# conbrio_pots_board_11-1-21.net
KiCad netlist of a schematic drawn in EAGLE
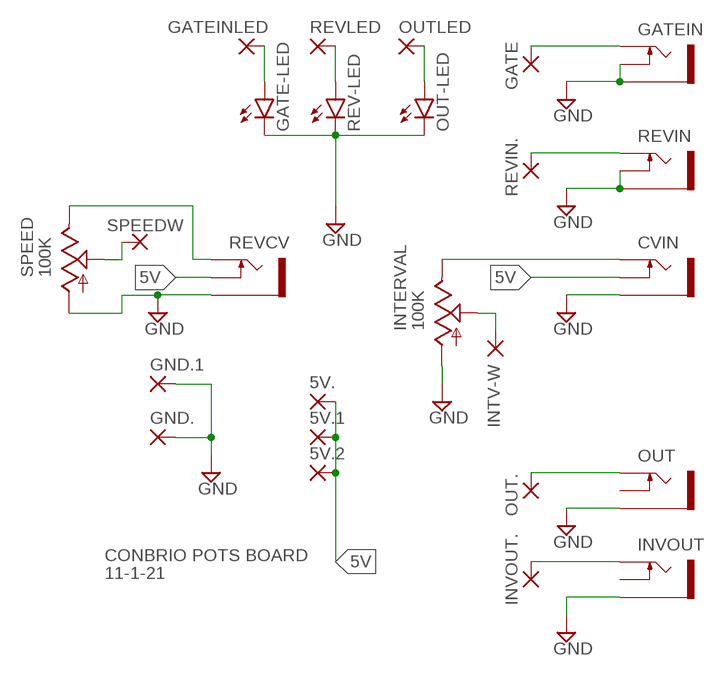
[diagram p0: schematic, sheet 1]

(export (version "E")
  (design (tool "Eeschema 10.0.6"))
  (components
    (comp (ref "5V.")
      (value "WIREPAD3,17/1,3")
      (footprint "eagle-import:3,17_1,3")
      (libsource (lib "eagle-import") (part "WIREPAD3,17/1,3"))
    )
    (comp (ref "5V.1")
      (value "WIREPAD3,17/1,3")
      (footprint "eagle-import:3,17_1,3")
      (libsource (lib "eagle-import") (part "WIREPAD3,17/1,3"))
    )
    (comp (ref "5V.2")
      (value "WIREPAD3,17/1,3")
      (footprint "eagle-import:3,17_1,3")
      (libsource (lib "eagle-import") (part "WIREPAD3,17/1,3"))
    )
    (comp (ref "CVIN")
      (value "THONKICONNNEW")
      (footprint "eagle-import:WQP-PJ301M-12_JACK")
      (libsource (lib "eagle-import") (part "THONKICONNNEW"))
    )
    (comp (ref "GATE")
      (value "WIREPAD3,17/1,3")
      (footprint "eagle-import:3,17_1,3")
      (libsource (lib "eagle-import") (part "WIREPAD3,17/1,3"))
    )
    (comp (ref "GATE-LED")
      (value "LED3MM")
      (footprint "eagle-import:LED3MM")
      (libsource (lib "eagle-import") (part "LED3MM"))
    )
    (comp (ref "GATEIN")
      (value "THONKICONNNEW")
      (footprint "eagle-import:WQP-PJ301M-12_JACK")
      (libsource (lib "eagle-import") (part "THONKICONNNEW"))
    )
    (comp (ref "GATEINLED")
      (value "WIREPAD3,17/1,3")
      (footprint "eagle-import:3,17_1,3")
      (libsource (lib "eagle-import") (part "WIREPAD3,17/1,3"))
    )
    (comp (ref "GND.")
      (value "WIREPAD3,17/1,3")
      (footprint "eagle-import:3,17_1,3")
      (libsource (lib "eagle-import") (part "WIREPAD3,17/1,3"))
    )
    (comp (ref "GND.1")
      (value "WIREPAD3,17/1,3")
      (footprint "eagle-import:3,17_1,3")
      (libsource (lib "eagle-import") (part "WIREPAD3,17/1,3"))
    )
    (comp (ref "INTERVAL")
      (value "100K")
      (footprint "eagle-import:9MM_SNAP-IN_POT")
      (libsource (lib "eagle-import") (part "9MM_SNAP-IN_POT_"))
    )
    (comp (ref "INTV-W")
      (value "WIREPAD3,17/1,3")
      (footprint "eagle-import:3,17_1,3")
      (libsource (lib "eagle-import") (part "WIREPAD3,17/1,3"))
    )
    (comp (ref "INVOUT")
      (value "THONKICONNNEW")
      (footprint "eagle-import:WQP-PJ301M-12_JACK")
      (libsource (lib "eagle-import") (part "THONKICONNNEW"))
    )
    (comp (ref "INVOUT.")
      (value "WIREPAD3,17/1,3")
      (footprint "eagle-import:3,17_1,3")
      (libsource (lib "eagle-import") (part "WIREPAD3,17/1,3"))
    )
    (comp (ref "OUT")
      (value "THONKICONNNEW")
      (footprint "eagle-import:WQP-PJ301M-12_JACK")
      (libsource (lib "eagle-import") (part "THONKICONNNEW"))
    )
    (comp (ref "OUT-LED")
      (value "LED3MM")
      (footprint "eagle-import:LED3MM")
      (libsource (lib "eagle-import") (part "LED3MM"))
    )
    (comp (ref "OUT.")
      (value "WIREPAD3,17/1,3")
      (footprint "eagle-import:3,17_1,3")
      (libsource (lib "eagle-import") (part "WIREPAD3,17/1,3"))
    )
    (comp (ref "OUTLED")
      (value "WIREPAD3,17/1,3")
      (footprint "eagle-import:3,17_1,3")
      (libsource (lib "eagle-import") (part "WIREPAD3,17/1,3"))
    )
    (comp (ref "REV-LED")
      (value "LED3MM")
      (footprint "eagle-import:LED3MM")
      (libsource (lib "eagle-import") (part "LED3MM"))
    )
    (comp (ref "REVCV")
      (value "THONKICONNNEW")
      (footprint "eagle-import:WQP-PJ301M-12_JACK")
      (libsource (lib "eagle-import") (part "THONKICONNNEW"))
    )
    (comp (ref "REVIN")
      (value "THONKICONNNEW")
      (footprint "eagle-import:WQP-PJ301M-12_JACK")
      (libsource (lib "eagle-import") (part "THONKICONNNEW"))
    )
    (comp (ref "REVIN.")
      (value "WIREPAD3,17/1,3")
      (footprint "eagle-import:3,17_1,3")
      (libsource (lib "eagle-import") (part "WIREPAD3,17/1,3"))
    )
    (comp (ref "REVLED")
      (value "WIREPAD3,17/1,3")
      (footprint "eagle-import:3,17_1,3")
      (libsource (lib "eagle-import") (part "WIREPAD3,17/1,3"))
    )
    (comp (ref "SPEED")
      (value "100K")
      (footprint "eagle-import:9MM_SNAP-IN_POT")
      (libsource (lib "eagle-import") (part "9MM_SNAP-IN_POT_"))
    )
    (comp (ref "SPEEDW")
      (value "WIREPAD3,17/1,3")
      (footprint "eagle-import:3,17_1,3")
      (libsource (lib "eagle-import") (part "WIREPAD3,17/1,3"))
    )
  )
  (nets
    (net (code "1") (name "5V") (class "Default")
      (node (ref "5V.") (pin "1") (pinfunction "P_1") (pintype "passive"))
      (node (ref "5V.1") (pin "1") (pinfunction "P_1") (pintype "passive"))
      (node (ref "5V.2") (pin "1") (pinfunction "P_1") (pintype "passive"))
      (node (ref "CVIN") (pin "P$2_SWITCH") (pinfunction "SWITCH_P$2_SWITCH") (pintype "passive"))
      (node (ref "REVCV") (pin "P$2_SWITCH") (pinfunction "SWITCH_P$2_SWITCH") (pintype "passive"))
    )
    (net (code "2") (name "GND") (class "Default")
      (node (ref "CVIN") (pin "P$3_SLEEVE") (pinfunction "SLEEVE_P$3_SLEEVE") (pintype "passive"))
      (node (ref "GATE-LED") (pin "K") (pinfunction "C_K") (pintype "passive"))
      (node (ref "GATEIN") (pin "P$2_SWITCH") (pinfunction "SWITCH_P$2_SWITCH") (pintype "passive"))
      (node (ref "GATEIN") (pin "P$3_SLEEVE") (pinfunction "SLEEVE_P$3_SLEEVE") (pintype "passive"))
      (node (ref "GND.") (pin "1") (pinfunction "P_1") (pintype "passive"))
      (node (ref "GND.1") (pin "1") (pinfunction "P_1") (pintype "passive"))
      (node (ref "INTERVAL") (pin "1") (pinfunction "A_1") (pintype "passive"))
      (node (ref "INVOUT") (pin "P$3_SLEEVE") (pinfunction "SLEEVE_P$3_SLEEVE") (pintype "passive"))
      (node (ref "OUT") (pin "P$3_SLEEVE") (pinfunction "SLEEVE_P$3_SLEEVE") (pintype "passive"))
      (node (ref "OUT-LED") (pin "K") (pinfunction "C_K") (pintype "passive"))
      (node (ref "REV-LED") (pin "K") (pinfunction "C_K") (pintype "passive"))
      (node (ref "REVCV") (pin "P$3_SLEEVE") (pinfunction "SLEEVE_P$3_SLEEVE") (pintype "passive"))
      (node (ref "REVIN") (pin "P$2_SWITCH") (pinfunction "SWITCH_P$2_SWITCH") (pintype "passive"))
      (node (ref "REVIN") (pin "P$3_SLEEVE") (pinfunction "SLEEVE_P$3_SLEEVE") (pintype "passive"))
      (node (ref "SPEED") (pin "1") (pinfunction "A_1") (pintype "passive"))
    )
    (net (code "3") (name "Net-(CVIN-TIP)") (class "Default")
      (node (ref "CVIN") (pin "P$1_TIP") (pinfunction "TIP_P$1_TIP") (pintype "passive"))
      (node (ref "INTERVAL") (pin "3") (pinfunction "E_3") (pintype "passive"))
    )
    (net (code "4") (name "Net-(GATE-P)") (class "Default")
      (node (ref "GATE") (pin "1") (pinfunction "P_1") (pintype "passive"))
      (node (ref "GATEIN") (pin "P$1_TIP") (pinfunction "TIP_P$1_TIP") (pintype "passive"))
    )
    (net (code "5") (name "Net-(GATEINLED-P)") (class "Default")
      (node (ref "GATE-LED") (pin "A") (pinfunction "A_A") (pintype "passive"))
      (node (ref "GATEINLED") (pin "1") (pinfunction "P_1") (pintype "passive"))
    )
    (net (code "6") (name "Net-(INTERVAL-S)") (class "Default")
      (node (ref "INTERVAL") (pin "2") (pinfunction "S_2") (pintype "passive"))
      (node (ref "INTV-W") (pin "1") (pinfunction "P_1") (pintype "passive"))
    )
    (net (code "7") (name "Net-(INVOUT-TIP)") (class "Default")
      (node (ref "INVOUT") (pin "P$1_TIP") (pinfunction "TIP_P$1_TIP") (pintype "passive"))
      (node (ref "INVOUT.") (pin "1") (pinfunction "P_1") (pintype "passive"))
    )
    (net (code "8") (name "Net-(OUT-TIP)") (class "Default")
      (node (ref "OUT") (pin "P$1_TIP") (pinfunction "TIP_P$1_TIP") (pintype "passive"))
      (node (ref "OUT.") (pin "1") (pinfunction "P_1") (pintype "passive"))
    )
    (net (code "9") (name "Net-(OUTLED-P)") (class "Default")
      (node (ref "OUT-LED") (pin "A") (pinfunction "A_A") (pintype "passive"))
      (node (ref "OUTLED") (pin "1") (pinfunction "P_1") (pintype "passive"))
    )
    (net (code "10") (name "Net-(REVCV-TIP)") (class "Default")
      (node (ref "REVCV") (pin "P$1_TIP") (pinfunction "TIP_P$1_TIP") (pintype "passive"))
      (node (ref "SPEED") (pin "3") (pinfunction "E_3") (pintype "passive"))
    )
    (net (code "11") (name "Net-(REVIN-TIP)") (class "Default")
      (node (ref "REVIN") (pin "P$1_TIP") (pinfunction "TIP_P$1_TIP") (pintype "passive"))
      (node (ref "REVIN.") (pin "1") (pinfunction "P_1") (pintype "passive"))
    )
    (net (code "12") (name "Net-(REVLED-P)") (class "Default")
      (node (ref "REV-LED") (pin "A") (pinfunction "A_A") (pintype "passive"))
      (node (ref "REVLED") (pin "1") (pinfunction "P_1") (pintype "passive"))
    )
    (net (code "13") (name "Net-(SPEED-S)") (class "Default")
      (node (ref "SPEED") (pin "2") (pinfunction "S_2") (pintype "passive"))
      (node (ref "SPEEDW") (pin "1") (pinfunction "P_1") (pintype "passive"))
    )
    (net (code "14") (name "unconnected-(INVOUT-SWITCH-PadP$2_SWITCH)") (class "Default")
      (node (ref "INVOUT") (pin "P$2_SWITCH") (pinfunction "SWITCH_P$2_SWITCH") (pintype "passive"))
    )
    (net (code "15") (name "unconnected-(OUT-SWITCH-PadP$2_SWITCH)") (class "Default")
      (node (ref "OUT") (pin "P$2_SWITCH") (pinfunction "SWITCH_P$2_SWITCH") (pintype "passive"))
    )
  )
)
